# untitled.net
KiCad netlist of a schematic drawn in EAGLE
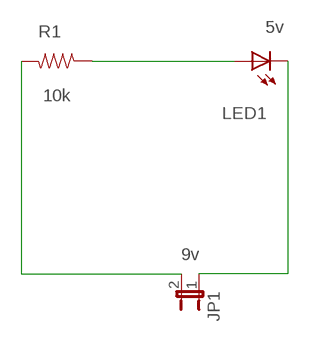
[diagram p0: schematic, sheet 1]

(export (version "E")
  (design (tool "Eeschema 10.0.6"))
  (components
    (comp (ref "JP1")
      (value "9v")
      (footprint "eagle-import:JP1")
      (libsource (lib "eagle-import") (part "JP1E"))
    )
    (comp (ref "LED1")
      (value "5v")
      (footprint "eagle-import:CHIP-LED0603")
      (libsource (lib "eagle-import") (part "LEDCHIP-LED0603"))
    )
    (comp (ref "R1")
      (value "10k")
      (footprint "eagle-import:0603")
      (libsource (lib "eagle-import") (part "10KOHM-0603-1/10W-1%"))
    )
  )
  (nets
    (net (code "1") (name "Net-(JP1-Pad1)") (class "Default")
      (node (ref "JP1") (pin "1") (pinfunction "1_1") (pintype "passive"))
      (node (ref "LED1") (pin "C") (pinfunction "C_C") (pintype "passive"))
    )
    (net (code "2") (name "Net-(JP1-Pad2)") (class "Default")
      (node (ref "JP1") (pin "2") (pinfunction "2_2") (pintype "passive"))
      (node (ref "R1") (pin "2") (pinfunction "2_2") (pintype "passive"))
    )
    (net (code "3") (name "Net-(LED1-PadA)") (class "Default")
      (node (ref "LED1") (pin "A") (pinfunction "A_A") (pintype "passive"))
      (node (ref "R1") (pin "1") (pinfunction "1_1") (pintype "passive"))
    )
  )
)
